# SergeVCO.net
KiCad netlist of a schematic drawn in EAGLE
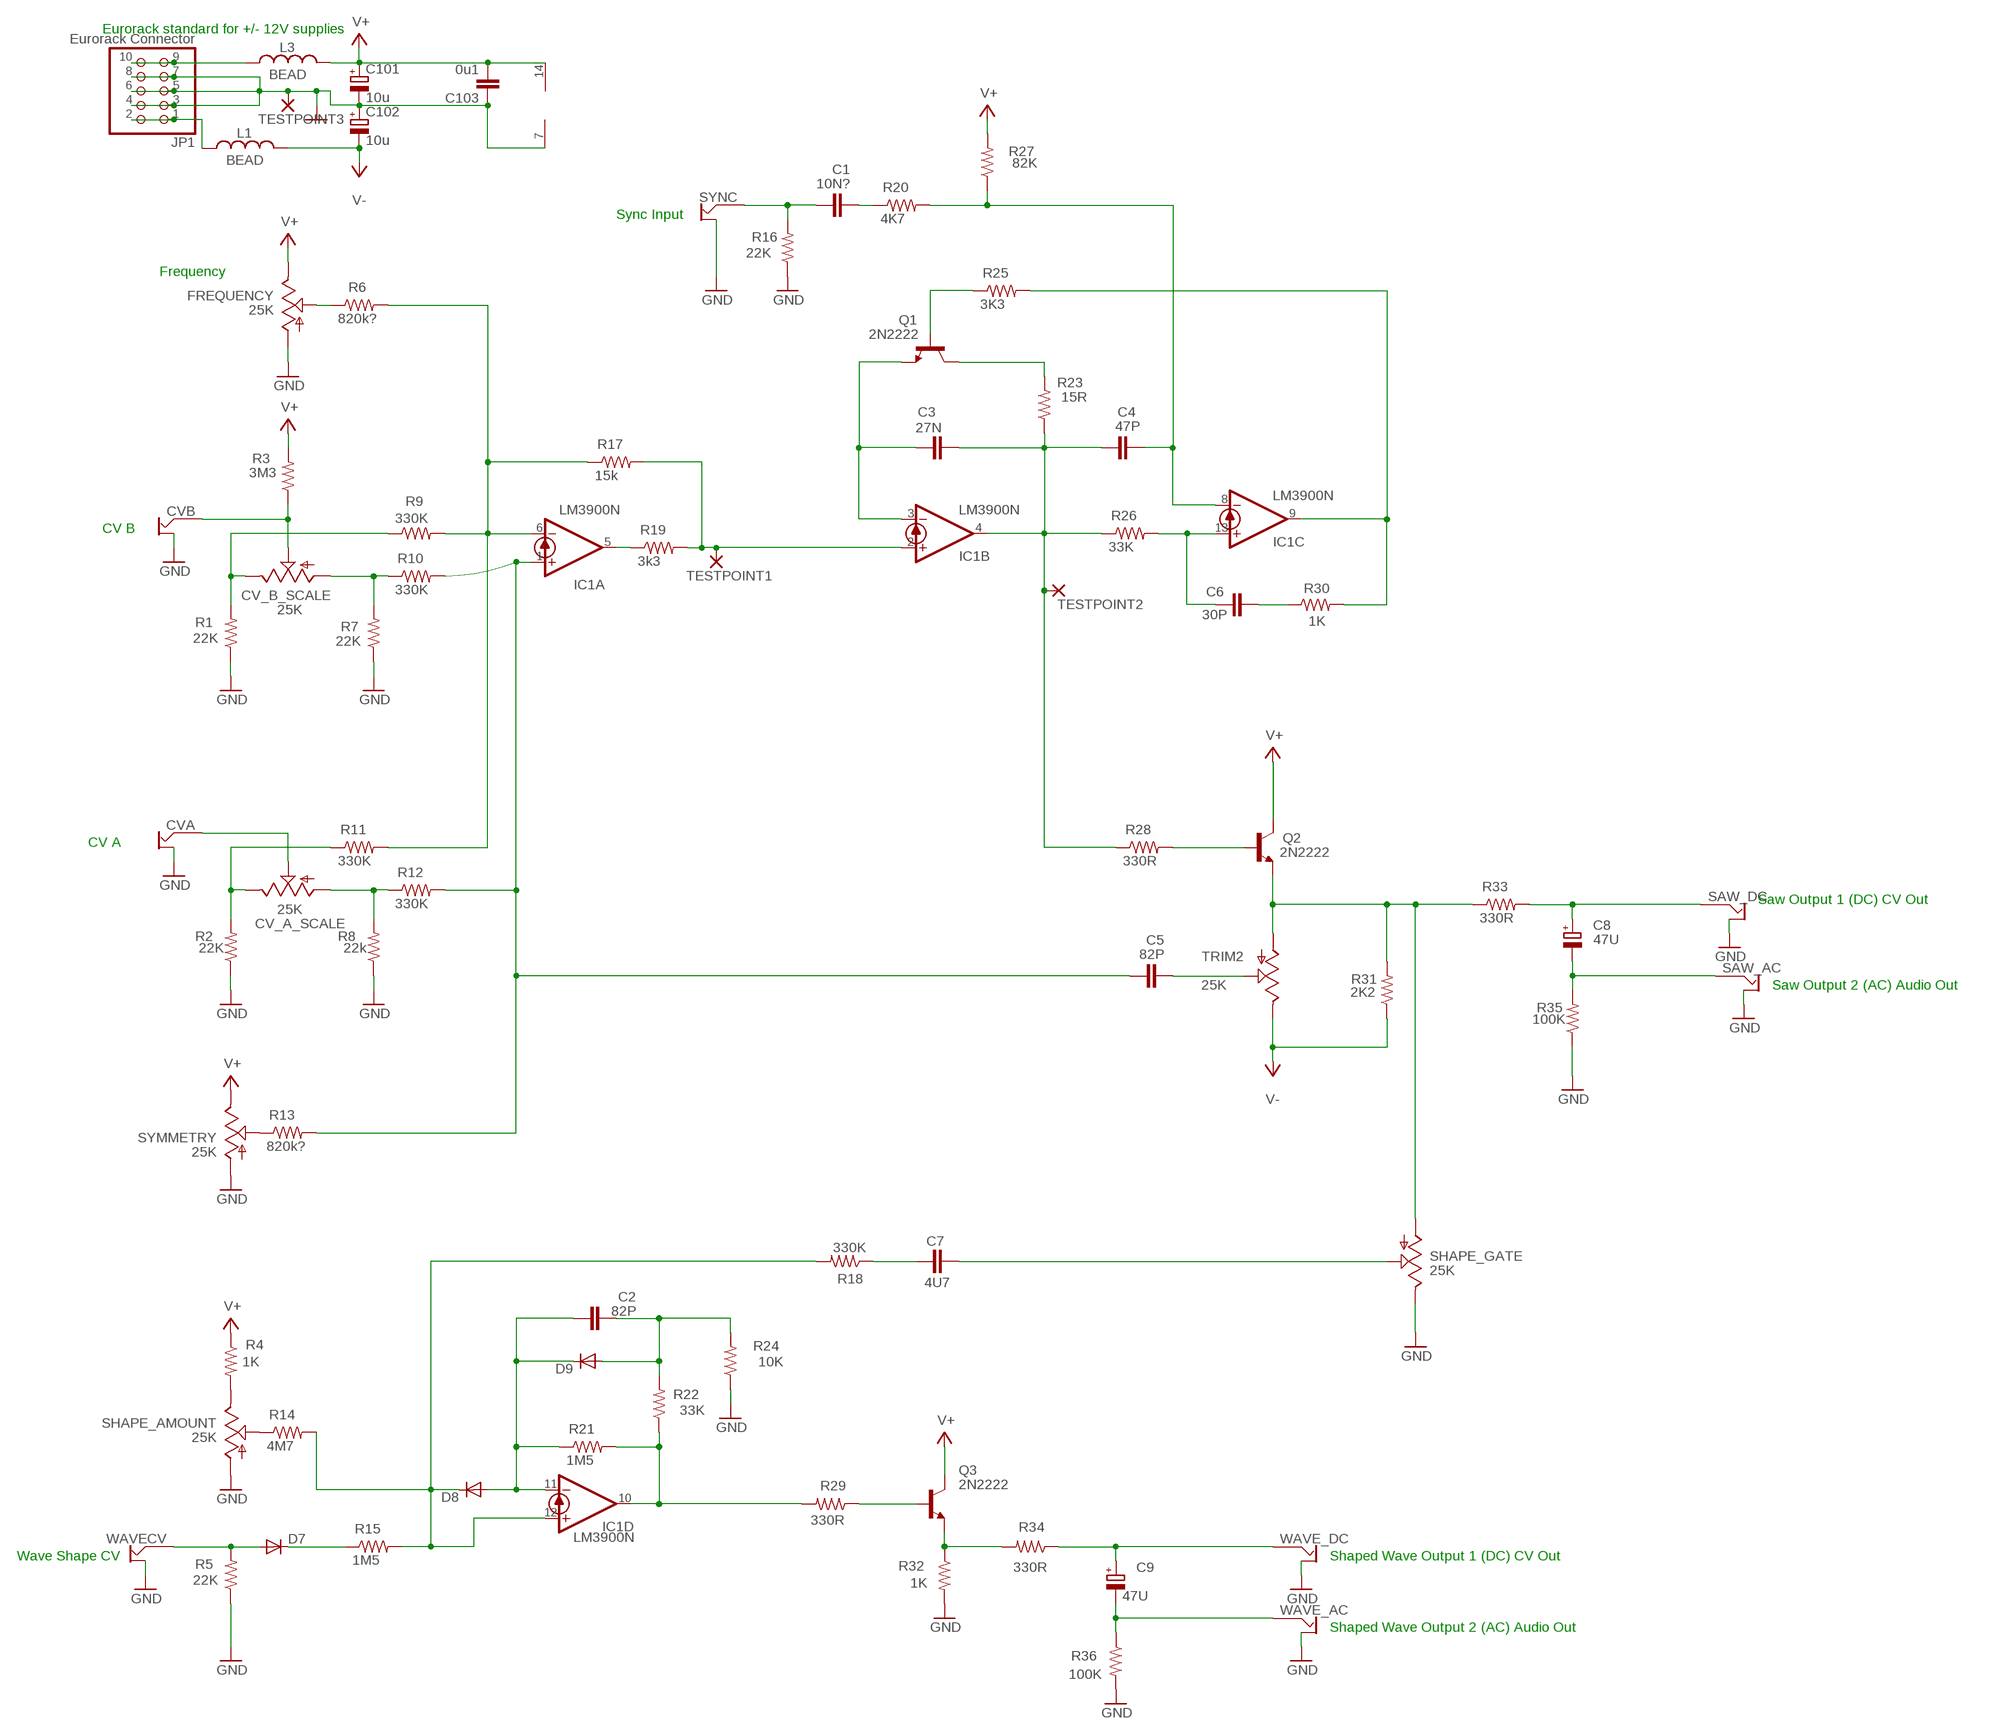
[diagram p0: schematic, sheet 1]

(export (version "E")
  (design (tool "Eeschema 10.0.6"))
  (components
    (comp (ref "C1")
      (value "10N?")
      (footprint "eagle-import:C050-025X075-AARON")
      (libsource (lib "eagle-import") (part "C-EU050-025X075-AARON"))
    )
    (comp (ref "C2")
      (value "82P")
      (footprint "eagle-import:C050-025X075-AARON")
      (libsource (lib "eagle-import") (part "C-EU050-025X075-AARON"))
    )
    (comp (ref "C3")
      (value "27N")
      (footprint "eagle-import:C050-025X075-AARON")
      (libsource (lib "eagle-import") (part "C-EU050-025X075-AARON"))
    )
    (comp (ref "C4")
      (value "47P")
      (footprint "eagle-import:C050-025X075-AARON")
      (libsource (lib "eagle-import") (part "C-EU050-025X075-AARON"))
    )
    (comp (ref "C5")
      (value "82P")
      (footprint "eagle-import:C050-025X075-AARON")
      (libsource (lib "eagle-import") (part "C-EU050-025X075-AARON"))
    )
    (comp (ref "C6")
      (value "30P")
      (footprint "eagle-import:C050-025X075-AARON")
      (libsource (lib "eagle-import") (part "C-EU050-025X075-AARON"))
    )
    (comp (ref "C7")
      (value "4U7")
      (footprint "eagle-import:C050-025X075-AARON")
      (libsource (lib "eagle-import") (part "C-EU050-025X075-AARON"))
    )
    (comp (ref "C8")
      (value "47U")
      (footprint "eagle-import:E1,8-4")
      (libsource (lib "eagle-import") (part "CPOL-EUE1.8-4"))
    )
    (comp (ref "C9")
      (value "47U")
      (footprint "eagle-import:E1,8-4")
      (libsource (lib "eagle-import") (part "CPOL-EUE1.8-4"))
    )
    (comp (ref "C101")
      (value "10u")
      (footprint "eagle-import:E1,8-4")
      (libsource (lib "eagle-import") (part "CPOL-EUE1.8-4"))
    )
    (comp (ref "C102")
      (value "10u")
      (footprint "eagle-import:E1,8-4")
      (libsource (lib "eagle-import") (part "CPOL-EUE1.8-4"))
    )
    (comp (ref "C103")
      (value "0u1")
      (footprint "eagle-import:C050-025X075-AARON")
      (libsource (lib "eagle-import") (part "C-EU050-025X075-AARON"))
    )
    (comp (ref "CVA")
      (value "OFFBOARD2JACKALT_AARON")
      (footprint "eagle-import:OFFBOARD2JACKALT")
      (libsource (lib "eagle-import") (part "OFFBOARD2JACKALT_AARON"))
    )
    (comp (ref "CVB")
      (value "OFFBOARD2JACKALT_AARON")
      (footprint "eagle-import:OFFBOARD2JACKALT")
      (libsource (lib "eagle-import") (part "OFFBOARD2JACKALT_AARON"))
    )
    (comp (ref "CV_A_SCALE")
      (value "25K")
      (footprint "eagle-import:B64Y")
      (libsource (lib "eagle-import") (part "TRIM_US-B64Y"))
    )
    (comp (ref "CV_B_SCALE")
      (value "25K")
      (footprint "eagle-import:B64Y")
      (libsource (lib "eagle-import") (part "TRIM_US-B64Y"))
    )
    (comp (ref "D7")
      (value "SMALL_DIODEDO35-7")
      (footprint "eagle-import:DO35-7")
      (libsource (lib "eagle-import") (part "SMALL_DIODEDO35-7"))
    )
    (comp (ref "D8")
      (value "SMALL_DIODEDO35-7")
      (footprint "eagle-import:DO35-7")
      (libsource (lib "eagle-import") (part "SMALL_DIODEDO35-7"))
    )
    (comp (ref "D9")
      (value "SMALL_DIODEDO35-7")
      (footprint "eagle-import:DO35-7")
      (libsource (lib "eagle-import") (part "SMALL_DIODEDO35-7"))
    )
    (comp (ref "FREQUENCY")
      (value "25K")
      (footprint "eagle-import:B64Y")
      (libsource (lib "eagle-import") (part "TRIM_US-B64Y"))
    )
    (comp (ref "IC1")
      (value "LM3900N")
      (footprint "eagle-import:DIL14")
      (libsource (lib "eagle-import") (part "LM3900N"))
    )
    (comp (ref "JP1")
      (value "Eurorack Connector")
      (footprint "eagle-import:2X05")
      (libsource (lib "eagle-import") (part "PINHD-2X5"))
    )
    (comp (ref "L1")
      (value "BEAD")
      (footprint "eagle-import:0207_10")
      (libsource (lib "eagle-import") (part "L-US0207/10"))
    )
    (comp (ref "L3")
      (value "BEAD")
      (footprint "eagle-import:0207_10")
      (libsource (lib "eagle-import") (part "L-US0207/10"))
    )
    (comp (ref "Q1")
      (value "2N2222")
      (footprint "eagle-import:TO92-EBC-OVAL")
      (libsource (lib "eagle-import") (part "2N2222"))
    )
    (comp (ref "Q2")
      (value "2N2222")
      (footprint "eagle-import:TO92-EBC-OVAL")
      (libsource (lib "eagle-import") (part "2N2222"))
    )
    (comp (ref "Q3")
      (value "2N2222")
      (footprint "eagle-import:TO92-EBC-OVAL")
      (libsource (lib "eagle-import") (part "2N2222"))
    )
    (comp (ref "R1")
      (value "22K")
      (footprint "eagle-import:0207_10")
      (libsource (lib "eagle-import") (part "R-US_0207/10"))
    )
    (comp (ref "R2")
      (value "22K")
      (footprint "eagle-import:0207_10")
      (libsource (lib "eagle-import") (part "R-US_0207/10"))
    )
    (comp (ref "R3")
      (value "3M3")
      (footprint "eagle-import:0207_10")
      (libsource (lib "eagle-import") (part "R-US_0207/10"))
    )
    (comp (ref "R4")
      (value "1K")
      (footprint "eagle-import:0207_10")
      (libsource (lib "eagle-import") (part "R-US_0207/10"))
    )
    (comp (ref "R5")
      (value "22K")
      (footprint "eagle-import:0207_10")
      (libsource (lib "eagle-import") (part "R-US_0207/10"))
    )
    (comp (ref "R6")
      (value "820k?")
      (footprint "eagle-import:0207_10")
      (libsource (lib "eagle-import") (part "R-US_0207/10"))
    )
    (comp (ref "R7")
      (value "22K")
      (footprint "eagle-import:0207_10")
      (libsource (lib "eagle-import") (part "R-US_0207/10"))
    )
    (comp (ref "R8")
      (value "22k")
      (footprint "eagle-import:0207_10")
      (libsource (lib "eagle-import") (part "R-US_0207/10"))
    )
    (comp (ref "R9")
      (value "330K")
      (footprint "eagle-import:0207_10")
      (libsource (lib "eagle-import") (part "R-US_0207/10"))
    )
    (comp (ref "R10")
      (value "330K")
      (footprint "eagle-import:0207_10")
      (libsource (lib "eagle-import") (part "R-US_0207/10"))
    )
    (comp (ref "R11")
      (value "330K")
      (footprint "eagle-import:0207_10")
      (libsource (lib "eagle-import") (part "R-US_0207/10"))
    )
    (comp (ref "R12")
      (value "330K")
      (footprint "eagle-import:0207_10")
      (libsource (lib "eagle-import") (part "R-US_0207/10"))
    )
    (comp (ref "R13")
      (value "820k?")
      (footprint "eagle-import:0207_10")
      (libsource (lib "eagle-import") (part "R-US_0207/10"))
    )
    (comp (ref "R14")
      (value "4M7")
      (footprint "eagle-import:0207_10")
      (libsource (lib "eagle-import") (part "R-US_0207/10"))
    )
    (comp (ref "R15")
      (value "1M5")
      (footprint "eagle-import:0207_10")
      (libsource (lib "eagle-import") (part "R-US_0207/10"))
    )
    (comp (ref "R16")
      (value "22K")
      (footprint "eagle-import:0207_10")
      (libsource (lib "eagle-import") (part "R-US_0207/10"))
    )
    (comp (ref "R17")
      (value "15k")
      (footprint "eagle-import:0207_10")
      (libsource (lib "eagle-import") (part "R-US_0207/10"))
    )
    (comp (ref "R18")
      (value "330K")
      (footprint "eagle-import:0207_10")
      (libsource (lib "eagle-import") (part "R-US_0207/10"))
    )
    (comp (ref "R19")
      (value "3k3")
      (footprint "eagle-import:0207_10")
      (libsource (lib "eagle-import") (part "R-US_0207/10"))
    )
    (comp (ref "R20")
      (value "4K7")
      (footprint "eagle-import:0207_10")
      (libsource (lib "eagle-import") (part "R-US_0207/10"))
    )
    (comp (ref "R21")
      (value "1M5")
      (footprint "eagle-import:0207_10")
      (libsource (lib "eagle-import") (part "R-US_0207/10"))
    )
    (comp (ref "R22")
      (value "33K")
      (footprint "eagle-import:0207_10")
      (libsource (lib "eagle-import") (part "R-US_0207/10"))
    )
    (comp (ref "R23")
      (value "15R")
      (footprint "eagle-import:0207_10")
      (libsource (lib "eagle-import") (part "R-US_0207/10"))
    )
    (comp (ref "R24")
      (value "10K")
      (footprint "eagle-import:0207_10")
      (libsource (lib "eagle-import") (part "R-US_0207/10"))
    )
    (comp (ref "R25")
      (value "3K3")
      (footprint "eagle-import:0207_10")
      (libsource (lib "eagle-import") (part "R-US_0207/10"))
    )
    (comp (ref "R26")
      (value "33K")
      (footprint "eagle-import:0207_10")
      (libsource (lib "eagle-import") (part "R-US_0207/10"))
    )
    (comp (ref "R27")
      (value "82K")
      (footprint "eagle-import:0207_10")
      (libsource (lib "eagle-import") (part "R-US_0207/10"))
    )
    (comp (ref "R28")
      (value "330R")
      (footprint "eagle-import:0207_10")
      (libsource (lib "eagle-import") (part "R-US_0207/10"))
    )
    (comp (ref "R29")
      (value "330R")
      (footprint "eagle-import:0207_10")
      (libsource (lib "eagle-import") (part "R-US_0207/10"))
    )
    (comp (ref "R30")
      (value "1K")
      (footprint "eagle-import:0207_10")
      (libsource (lib "eagle-import") (part "R-US_0207/10"))
    )
    (comp (ref "R31")
      (value "2K2")
      (footprint "eagle-import:0207_10")
      (libsource (lib "eagle-import") (part "R-US_0207/10"))
    )
    (comp (ref "R32")
      (value "1K")
      (footprint "eagle-import:0207_10")
      (libsource (lib "eagle-import") (part "R-US_0207/10"))
    )
    (comp (ref "R33")
      (value "330R")
      (footprint "eagle-import:0207_10")
      (libsource (lib "eagle-import") (part "R-US_0207/10"))
    )
    (comp (ref "R34")
      (value "330R")
      (footprint "eagle-import:0207_10")
      (libsource (lib "eagle-import") (part "R-US_0207/10"))
    )
    (comp (ref "R35")
      (value "100K")
      (footprint "eagle-import:0207_10")
      (libsource (lib "eagle-import") (part "R-US_0207/10"))
    )
    (comp (ref "R36")
      (value "100K")
      (footprint "eagle-import:0207_10")
      (libsource (lib "eagle-import") (part "R-US_0207/10"))
    )
    (comp (ref "SAW_AC")
      (value "OFFBOARD2JACKALT_AARON")
      (footprint "eagle-import:OFFBOARD2JACKALT")
      (libsource (lib "eagle-import") (part "OFFBOARD2JACKALT_AARON"))
    )
    (comp (ref "SAW_DC")
      (value "OFFBOARD2JACKALT_AARON")
      (footprint "eagle-import:OFFBOARD2JACKALT")
      (libsource (lib "eagle-import") (part "OFFBOARD2JACKALT_AARON"))
    )
    (comp (ref "SHAPE_AMOUNT")
      (value "25K")
      (footprint "eagle-import:B64Y")
      (libsource (lib "eagle-import") (part "TRIM_US-B64Y"))
    )
    (comp (ref "SHAPE_GATE")
      (value "25K")
      (footprint "eagle-import:B64Y")
      (libsource (lib "eagle-import") (part "TRIM_US-B64Y"))
    )
    (comp (ref "SYMMETRY")
      (value "25K")
      (footprint "eagle-import:B64Y")
      (libsource (lib "eagle-import") (part "TRIM_US-B64Y"))
    )
    (comp (ref "SYNC")
      (value "OFFBOARD2JACKALT_AARON")
      (footprint "eagle-import:OFFBOARD2JACKALT")
      (libsource (lib "eagle-import") (part "OFFBOARD2JACKALT_AARON"))
    )
    (comp (ref "TESTPOINT1")
      (value "IOPAD_AARON")
      (footprint "eagle-import:ELLIPTICALPADSINGLE")
      (libsource (lib "eagle-import") (part "IOPAD_AARON"))
    )
    (comp (ref "TESTPOINT2")
      (value "IOPAD_AARON")
      (footprint "eagle-import:ELLIPTICALPADSINGLE")
      (libsource (lib "eagle-import") (part "IOPAD_AARON"))
    )
    (comp (ref "TESTPOINT3")
      (value "IOPAD_AARON")
      (footprint "eagle-import:ELLIPTICALPADSINGLE")
      (libsource (lib "eagle-import") (part "IOPAD_AARON"))
    )
    (comp (ref "TRIM2")
      (value "25K")
      (footprint "eagle-import:RS3")
      (libsource (lib "eagle-import") (part "pot_331_TRIM_US-RS3"))
    )
    (comp (ref "WAVECV")
      (value "OFFBOARD2JACKALT_AARON")
      (footprint "eagle-import:OFFBOARD2JACKALT")
      (libsource (lib "eagle-import") (part "OFFBOARD2JACKALT_AARON"))
    )
    (comp (ref "WAVE_AC")
      (value "OFFBOARD2JACKALT_AARON")
      (footprint "eagle-import:OFFBOARD2JACKALT")
      (libsource (lib "eagle-import") (part "OFFBOARD2JACKALT_AARON"))
    )
    (comp (ref "WAVE_DC")
      (value "OFFBOARD2JACKALT_AARON")
      (footprint "eagle-import:OFFBOARD2JACKALT")
      (libsource (lib "eagle-import") (part "OFFBOARD2JACKALT_AARON"))
    )
  )
  (nets
    (net (code "1") (name "GND") (class "Default")
      (node (ref "C101") (pin "-") (pinfunction "-_-") (pintype "passive"))
      (node (ref "C102") (pin "+") (pinfunction "+_+") (pintype "passive"))
      (node (ref "C103") (pin "1") (pinfunction "1_1") (pintype "passive"))
      (node (ref "CVA") (pin "GND") (pinfunction "GND_GND") (pintype "passive"))
      (node (ref "CVB") (pin "GND") (pinfunction "GND_GND") (pintype "passive"))
      (node (ref "FREQUENCY") (pin "A") (pinfunction "A_A") (pintype "passive"))
      (node (ref "IC1") (pin "7") (pinfunction "GND_7") (pintype "power_in"))
      (node (ref "JP1") (pin "3") (pinfunction "3_3") (pintype "passive"))
      (node (ref "JP1") (pin "4") (pinfunction "4_4") (pintype "passive"))
      (node (ref "JP1") (pin "5") (pinfunction "5_5") (pintype "passive"))
      (node (ref "JP1") (pin "6") (pinfunction "6_6") (pintype "passive"))
      (node (ref "JP1") (pin "7") (pinfunction "7_7") (pintype "passive"))
      (node (ref "JP1") (pin "8") (pinfunction "8_8") (pintype "passive"))
      (node (ref "R1") (pin "1") (pinfunction "1_1") (pintype "passive"))
      (node (ref "R16") (pin "1") (pinfunction "1_1") (pintype "passive"))
      (node (ref "R2") (pin "1") (pinfunction "1_1") (pintype "passive"))
      (node (ref "R24") (pin "1") (pinfunction "1_1") (pintype "passive"))
      (node (ref "R32") (pin "2") (pinfunction "2_2") (pintype "passive"))
      (node (ref "R35") (pin "1") (pinfunction "1_1") (pintype "passive"))
      (node (ref "R36") (pin "2") (pinfunction "2_2") (pintype "passive"))
      (node (ref "R5") (pin "1") (pinfunction "1_1") (pintype "passive"))
      (node (ref "R7") (pin "1") (pinfunction "1_1") (pintype "passive"))
      (node (ref "R8") (pin "1") (pinfunction "1_1") (pintype "passive"))
      (node (ref "SAW_AC") (pin "GND") (pinfunction "GND_GND") (pintype "passive"))
      (node (ref "SAW_DC") (pin "GND") (pinfunction "GND_GND") (pintype "passive"))
      (node (ref "SHAPE_AMOUNT") (pin "A") (pinfunction "A_A") (pintype "passive"))
      (node (ref "SHAPE_GATE") (pin "E") (pinfunction "E_E") (pintype "passive"))
      (node (ref "SYMMETRY") (pin "A") (pinfunction "A_A") (pintype "passive"))
      (node (ref "SYNC") (pin "GND") (pinfunction "GND_GND") (pintype "passive"))
      (node (ref "TESTPOINT3") (pin "P$1") (pinfunction "P_P$1") (pintype "passive"))
      (node (ref "WAVECV") (pin "GND") (pinfunction "GND_GND") (pintype "passive"))
      (node (ref "WAVE_AC") (pin "GND") (pinfunction "GND_GND") (pintype "passive"))
      (node (ref "WAVE_DC") (pin "GND") (pinfunction "GND_GND") (pintype "passive"))
    )
    (net (code "2") (name "Net-(C1-Pad1)") (class "Default")
      (node (ref "C1") (pin "1") (pinfunction "1_1") (pintype "passive"))
      (node (ref "R16") (pin "2") (pinfunction "2_2") (pintype "passive"))
      (node (ref "SYNC") (pin "SIGNAL") (pinfunction "SIGNAL_SIGNAL") (pintype "passive"))
    )
    (net (code "3") (name "Net-(C1-Pad2)") (class "Default")
      (node (ref "C1") (pin "2") (pinfunction "2_2") (pintype "passive"))
      (node (ref "R20") (pin "1") (pinfunction "1_1") (pintype "passive"))
    )
    (net (code "4") (name "Net-(C2-Pad2)") (class "Default")
      (node (ref "C2") (pin "2") (pinfunction "2_2") (pintype "passive"))
      (node (ref "D9") (pin "A") (pinfunction "A_A") (pintype "passive"))
      (node (ref "R22") (pin "2") (pinfunction "2_2") (pintype "passive"))
      (node (ref "R24") (pin "2") (pinfunction "2_2") (pintype "passive"))
    )
    (net (code "5") (name "Net-(C5-Pad2)") (class "Default")
      (node (ref "C5") (pin "2") (pinfunction "2_2") (pintype "passive"))
      (node (ref "TRIM2") (pin "S") (pinfunction "S_S") (pintype "passive"))
    )
    (net (code "6") (name "Net-(C6-Pad2)") (class "Default")
      (node (ref "C6") (pin "2") (pinfunction "2_2") (pintype "passive"))
      (node (ref "R30") (pin "1") (pinfunction "1_1") (pintype "passive"))
    )
    (net (code "7") (name "Net-(C7-Pad1)") (class "Default")
      (node (ref "C7") (pin "1") (pinfunction "1_1") (pintype "passive"))
      (node (ref "R18") (pin "1") (pinfunction "1_1") (pintype "passive"))
    )
    (net (code "8") (name "Net-(C7-Pad2)") (class "Default")
      (node (ref "C7") (pin "2") (pinfunction "2_2") (pintype "passive"))
      (node (ref "SHAPE_GATE") (pin "S") (pinfunction "S_S") (pintype "passive"))
    )
    (net (code "9") (name "Net-(C8-Pad+)") (class "Default")
      (node (ref "C8") (pin "+") (pinfunction "+_+") (pintype "passive"))
      (node (ref "R33") (pin "2") (pinfunction "2_2") (pintype "passive"))
      (node (ref "SAW_DC") (pin "SIGNAL") (pinfunction "SIGNAL_SIGNAL") (pintype "passive"))
    )
    (net (code "10") (name "Net-(C8-Pad-)") (class "Default")
      (node (ref "C8") (pin "-") (pinfunction "-_-") (pintype "passive"))
      (node (ref "R35") (pin "2") (pinfunction "2_2") (pintype "passive"))
      (node (ref "SAW_AC") (pin "SIGNAL") (pinfunction "SIGNAL_SIGNAL") (pintype "passive"))
    )
    (net (code "11") (name "Net-(C9-Pad+)") (class "Default")
      (node (ref "C9") (pin "+") (pinfunction "+_+") (pintype "passive"))
      (node (ref "R34") (pin "1") (pinfunction "1_1") (pintype "passive"))
      (node (ref "WAVE_DC") (pin "SIGNAL") (pinfunction "SIGNAL_SIGNAL") (pintype "passive"))
    )
    (net (code "12") (name "Net-(C9-Pad-)") (class "Default")
      (node (ref "C9") (pin "-") (pinfunction "-_-") (pintype "passive"))
      (node (ref "R36") (pin "1") (pinfunction "1_1") (pintype "passive"))
      (node (ref "WAVE_AC") (pin "SIGNAL") (pinfunction "SIGNAL_SIGNAL") (pintype "passive"))
    )
    (net (code "13") (name "Net-(CVA-PadSIGNAL)") (class "Default")
      (node (ref "CVA") (pin "SIGNAL") (pinfunction "SIGNAL_SIGNAL") (pintype "passive"))
      (node (ref "CV_A_SCALE") (pin "S") (pinfunction "S_S") (pintype "passive"))
    )
    (net (code "14") (name "Net-(CVB-PadSIGNAL)") (class "Default")
      (node (ref "CVB") (pin "SIGNAL") (pinfunction "SIGNAL_SIGNAL") (pintype "passive"))
      (node (ref "CV_B_SCALE") (pin "S") (pinfunction "S_S") (pintype "passive"))
      (node (ref "R3") (pin "1") (pinfunction "1_1") (pintype "passive"))
    )
    (net (code "15") (name "Net-(CV_A_SCALE-PadA)") (class "Default")
      (node (ref "CV_A_SCALE") (pin "A") (pinfunction "A_A") (pintype "passive"))
      (node (ref "R12") (pin "1") (pinfunction "1_1") (pintype "passive"))
      (node (ref "R8") (pin "2") (pinfunction "2_2") (pintype "passive"))
    )
    (net (code "16") (name "Net-(CV_A_SCALE-PadE)") (class "Default")
      (node (ref "CV_A_SCALE") (pin "E") (pinfunction "E_E") (pintype "passive"))
      (node (ref "R11") (pin "1") (pinfunction "1_1") (pintype "passive"))
      (node (ref "R2") (pin "2") (pinfunction "2_2") (pintype "passive"))
    )
    (net (code "17") (name "Net-(CV_B_SCALE-PadA)") (class "Default")
      (node (ref "CV_B_SCALE") (pin "A") (pinfunction "A_A") (pintype "passive"))
      (node (ref "R10") (pin "1") (pinfunction "1_1") (pintype "passive"))
      (node (ref "R7") (pin "2") (pinfunction "2_2") (pintype "passive"))
    )
    (net (code "18") (name "Net-(CV_B_SCALE-PadE)") (class "Default")
      (node (ref "CV_B_SCALE") (pin "E") (pinfunction "E_E") (pintype "passive"))
      (node (ref "R1") (pin "2") (pinfunction "2_2") (pintype "passive"))
      (node (ref "R9") (pin "1") (pinfunction "1_1") (pintype "passive"))
    )
    (net (code "19") (name "Net-(D7-PadA)") (class "Default")
      (node (ref "D7") (pin "A") (pinfunction "A_A") (pintype "passive"))
      (node (ref "R5") (pin "2") (pinfunction "2_2") (pintype "passive"))
      (node (ref "WAVECV") (pin "SIGNAL") (pinfunction "SIGNAL_SIGNAL") (pintype "passive"))
    )
    (net (code "20") (name "Net-(D7-PadC)") (class "Default")
      (node (ref "D7") (pin "C") (pinfunction "C_C") (pintype "passive"))
      (node (ref "R15") (pin "1") (pinfunction "1_1") (pintype "passive"))
    )
    (net (code "21") (name "Net-(FREQUENCY-PadS)") (class "Default")
      (node (ref "FREQUENCY") (pin "S") (pinfunction "S_S") (pintype "passive"))
      (node (ref "R6") (pin "1") (pinfunction "1_1") (pintype "passive"))
    )
    (net (code "22") (name "Net-(IC1A-+IN)") (class "Default")
      (node (ref "C5") (pin "1") (pinfunction "1_1") (pintype "passive"))
      (node (ref "IC1") (pin "1") (pinfunction "+IN_1") (pintype "input"))
      (node (ref "R10") (pin "2") (pinfunction "2_2") (pintype "passive"))
      (node (ref "R12") (pin "2") (pinfunction "2_2") (pintype "passive"))
      (node (ref "R13") (pin "2") (pinfunction "2_2") (pintype "passive"))
    )
    (net (code "23") (name "Net-(IC1A--IN)") (class "Default")
      (node (ref "IC1") (pin "6") (pinfunction "-IN_6") (pintype "input"))
      (node (ref "R11") (pin "2") (pinfunction "2_2") (pintype "passive"))
      (node (ref "R17") (pin "1") (pinfunction "1_1") (pintype "passive"))
      (node (ref "R6") (pin "2") (pinfunction "2_2") (pintype "passive"))
      (node (ref "R9") (pin "2") (pinfunction "2_2") (pintype "passive"))
    )
    (net (code "24") (name "Net-(IC1A-OUT)") (class "Default")
      (node (ref "IC1") (pin "5") (pinfunction "OUT_5") (pintype "output"))
      (node (ref "R19") (pin "1") (pinfunction "1_1") (pintype "passive"))
    )
    (net (code "25") (name "Net-(IC1B-+IN)") (class "Default")
      (node (ref "IC1") (pin "2") (pinfunction "+IN_2") (pintype "input"))
      (node (ref "R17") (pin "2") (pinfunction "2_2") (pintype "passive"))
      (node (ref "R19") (pin "2") (pinfunction "2_2") (pintype "passive"))
      (node (ref "TESTPOINT1") (pin "P$1") (pinfunction "P_P$1") (pintype "passive"))
    )
    (net (code "26") (name "Net-(IC1B--IN)") (class "Default")
      (node (ref "C3") (pin "1") (pinfunction "1_1") (pintype "passive"))
      (node (ref "IC1") (pin "3") (pinfunction "-IN_3") (pintype "input"))
      (node (ref "Q1") (pin "E") (pinfunction "E_E") (pintype "passive"))
    )
    (net (code "27") (name "Net-(IC1B-OUT)") (class "Default")
      (node (ref "C3") (pin "2") (pinfunction "2_2") (pintype "passive"))
      (node (ref "C4") (pin "1") (pinfunction "1_1") (pintype "passive"))
      (node (ref "IC1") (pin "4") (pinfunction "OUT_4") (pintype "output"))
      (node (ref "R23") (pin "1") (pinfunction "1_1") (pintype "passive"))
      (node (ref "R26") (pin "1") (pinfunction "1_1") (pintype "passive"))
      (node (ref "R28") (pin "1") (pinfunction "1_1") (pintype "passive"))
      (node (ref "TESTPOINT2") (pin "P$1") (pinfunction "P_P$1") (pintype "passive"))
    )
    (net (code "28") (name "Net-(IC1C-+IN)") (class "Default")
      (node (ref "C6") (pin "1") (pinfunction "1_1") (pintype "passive"))
      (node (ref "IC1") (pin "13") (pinfunction "+IN_13") (pintype "input"))
      (node (ref "R26") (pin "2") (pinfunction "2_2") (pintype "passive"))
    )
    (net (code "29") (name "Net-(IC1C--IN)") (class "Default")
      (node (ref "C4") (pin "2") (pinfunction "2_2") (pintype "passive"))
      (node (ref "IC1") (pin "8") (pinfunction "-IN_8") (pintype "input"))
      (node (ref "R20") (pin "2") (pinfunction "2_2") (pintype "passive"))
      (node (ref "R27") (pin "1") (pinfunction "1_1") (pintype "passive"))
    )
    (net (code "30") (name "Net-(IC1C-OUT)") (class "Default")
      (node (ref "IC1") (pin "9") (pinfunction "OUT_9") (pintype "output"))
      (node (ref "R25") (pin "2") (pinfunction "2_2") (pintype "passive"))
      (node (ref "R30") (pin "2") (pinfunction "2_2") (pintype "passive"))
    )
    (net (code "31") (name "Net-(IC1D-+IN)") (class "Default")
      (node (ref "D8") (pin "C") (pinfunction "C_C") (pintype "passive"))
      (node (ref "IC1") (pin "12") (pinfunction "+IN_12") (pintype "input"))
      (node (ref "R14") (pin "2") (pinfunction "2_2") (pintype "passive"))
      (node (ref "R15") (pin "2") (pinfunction "2_2") (pintype "passive"))
      (node (ref "R18") (pin "2") (pinfunction "2_2") (pintype "passive"))
    )
    (net (code "32") (name "Net-(IC1D--IN)") (class "Default")
      (node (ref "C2") (pin "1") (pinfunction "1_1") (pintype "passive"))
      (node (ref "D8") (pin "A") (pinfunction "A_A") (pintype "passive"))
      (node (ref "D9") (pin "C") (pinfunction "C_C") (pintype "passive"))
      (node (ref "IC1") (pin "11") (pinfunction "-IN_11") (pintype "input"))
      (node (ref "R21") (pin "1") (pinfunction "1_1") (pintype "passive"))
    )
    (net (code "33") (name "Net-(IC1D-OUT)") (class "Default")
      (node (ref "IC1") (pin "10") (pinfunction "OUT_10") (pintype "output"))
      (node (ref "R21") (pin "2") (pinfunction "2_2") (pintype "passive"))
      (node (ref "R22") (pin "1") (pinfunction "1_1") (pintype "passive"))
      (node (ref "R29") (pin "2") (pinfunction "2_2") (pintype "passive"))
    )
    (net (code "34") (name "Net-(JP1-Pad1)") (class "Default")
      (node (ref "JP1") (pin "1") (pinfunction "1_1") (pintype "passive"))
      (node (ref "JP1") (pin "2") (pinfunction "2_2") (pintype "passive"))
      (node (ref "L1") (pin "1") (pinfunction "1_1") (pintype "passive"))
    )
    (net (code "35") (name "Net-(JP1-Pad10)") (class "Default")
      (node (ref "JP1") (pin "10") (pinfunction "10_10") (pintype "passive"))
      (node (ref "JP1") (pin "9") (pinfunction "9_9") (pintype "passive"))
      (node (ref "L3") (pin "1") (pinfunction "1_1") (pintype "passive"))
    )
    (net (code "36") (name "Net-(Q1-PadB)") (class "Default")
      (node (ref "Q1") (pin "B") (pinfunction "B_B") (pintype "passive"))
      (node (ref "R25") (pin "1") (pinfunction "1_1") (pintype "passive"))
    )
    (net (code "37") (name "Net-(Q1-PadC)") (class "Default")
      (node (ref "Q1") (pin "C") (pinfunction "C_C") (pintype "passive"))
      (node (ref "R23") (pin "2") (pinfunction "2_2") (pintype "passive"))
    )
    (net (code "38") (name "Net-(Q2-PadB)") (class "Default")
      (node (ref "Q2") (pin "B") (pinfunction "B_B") (pintype "passive"))
      (node (ref "R28") (pin "2") (pinfunction "2_2") (pintype "passive"))
    )
    (net (code "39") (name "Net-(Q2-PadE)") (class "Default")
      (node (ref "Q2") (pin "E") (pinfunction "E_E") (pintype "passive"))
      (node (ref "R31") (pin "2") (pinfunction "2_2") (pintype "passive"))
      (node (ref "R33") (pin "1") (pinfunction "1_1") (pintype "passive"))
      (node (ref "SHAPE_GATE") (pin "A") (pinfunction "A_A") (pintype "passive"))
      (node (ref "TRIM2") (pin "A") (pinfunction "A_A") (pintype "passive"))
    )
    (net (code "40") (name "Net-(Q3-PadB)") (class "Default")
      (node (ref "Q3") (pin "B") (pinfunction "B_B") (pintype "passive"))
      (node (ref "R29") (pin "1") (pinfunction "1_1") (pintype "passive"))
    )
    (net (code "41") (name "Net-(Q3-PadE)") (class "Default")
      (node (ref "Q3") (pin "E") (pinfunction "E_E") (pintype "passive"))
      (node (ref "R32") (pin "1") (pinfunction "1_1") (pintype "passive"))
      (node (ref "R34") (pin "2") (pinfunction "2_2") (pintype "passive"))
    )
    (net (code "42") (name "Net-(R4-Pad2)") (class "Default")
      (node (ref "R4") (pin "2") (pinfunction "2_2") (pintype "passive"))
      (node (ref "SHAPE_AMOUNT") (pin "E") (pinfunction "E_E") (pintype "passive"))
    )
    (net (code "43") (name "Net-(R13-Pad1)") (class "Default")
      (node (ref "R13") (pin "1") (pinfunction "1_1") (pintype "passive"))
      (node (ref "SYMMETRY") (pin "S") (pinfunction "S_S") (pintype "passive"))
    )
    (net (code "44") (name "Net-(R14-Pad1)") (class "Default")
      (node (ref "R14") (pin "1") (pinfunction "1_1") (pintype "passive"))
      (node (ref "SHAPE_AMOUNT") (pin "S") (pinfunction "S_S") (pintype "passive"))
    )
    (net (code "45") (name "V+") (class "Default")
      (node (ref "C101") (pin "+") (pinfunction "+_+") (pintype "passive"))
      (node (ref "C103") (pin "2") (pinfunction "2_2") (pintype "passive"))
      (node (ref "FREQUENCY") (pin "E") (pinfunction "E_E") (pintype "passive"))
      (node (ref "IC1") (pin "14") (pinfunction "V+_14") (pintype "power_in"))
      (node (ref "L3") (pin "2") (pinfunction "2_2") (pintype "passive"))
      (node (ref "Q2") (pin "C") (pinfunction "C_C") (pintype "passive"))
      (node (ref "Q3") (pin "C") (pinfunction "C_C") (pintype "passive"))
      (node (ref "R27") (pin "2") (pinfunction "2_2") (pintype "passive"))
      (node (ref "R3") (pin "2") (pinfunction "2_2") (pintype "passive"))
      (node (ref "R4") (pin "1") (pinfunction "1_1") (pintype "passive"))
      (node (ref "SYMMETRY") (pin "E") (pinfunction "E_E") (pintype "passive"))
    )
    (net (code "46") (name "V-") (class "Default")
      (node (ref "C102") (pin "-") (pinfunction "-_-") (pintype "passive"))
      (node (ref "L1") (pin "2") (pinfunction "2_2") (pintype "passive"))
      (node (ref "R31") (pin "1") (pinfunction "1_1") (pintype "passive"))
      (node (ref "TRIM2") (pin "E") (pinfunction "E_E") (pintype "passive"))
    )
  )
)
